# log.net
KiCad netlist of a schematic drawn in Altium Designer
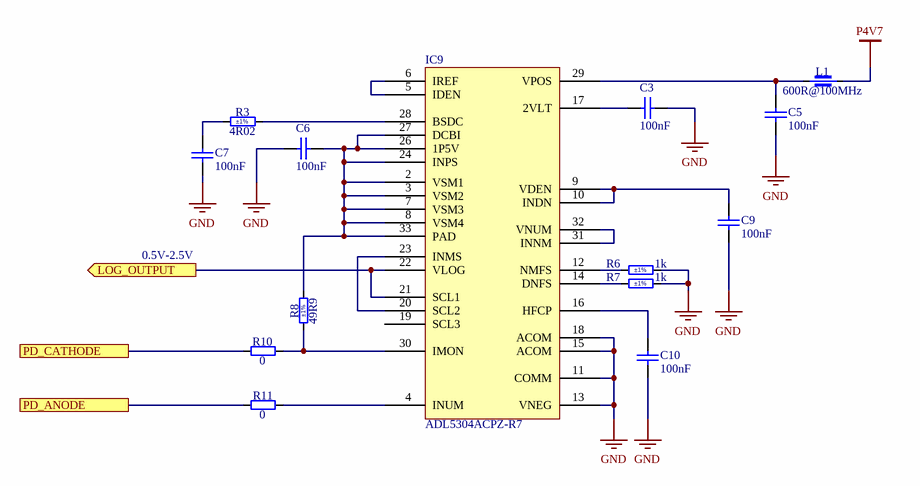
[diagram p0: log.SchDoc]

(export (version "E")
  (design (tool "Eeschema 10.0.6"))
  (components
    (comp (ref "C3")
      (value "100nF")
      (footprint "CAPC1005X55N")
      (description "Non-polarised capacitor")
      (fields
        (field (name "TOLERANCE") "±10%")
        (field (name "VOLTAGE") "16V")
        (field (name "AUTHOR") "CERN DEM JLC")
      )
      (libsource (lib "Capacitors") (part "Capacitor - non polarized"))
    )
    (comp (ref "C5")
      (value "100nF")
      (footprint "CAPC1005X55N")
      (description "Non-polarised capacitor")
      (fields
        (field (name "TOLERANCE") "±10%")
        (field (name "VOLTAGE") "16V")
        (field (name "AUTHOR") "CERN DEM JLC")
      )
      (libsource (lib "Capacitors") (part "Capacitor - non polarized"))
    )
    (comp (ref "C6")
      (value "100nF")
      (footprint "CAPC1005X55N")
      (description "Non-polarised capacitor")
      (fields
        (field (name "TOLERANCE") "±10%")
        (field (name "VOLTAGE") "16V")
        (field (name "AUTHOR") "CERN DEM JLC")
      )
      (libsource (lib "Capacitors") (part "Capacitor - non polarized"))
    )
    (comp (ref "C7")
      (value "100nF")
      (footprint "CAPC1005X55N")
      (description "Non-polarised capacitor")
      (fields
        (field (name "TOLERANCE") "±10%")
        (field (name "VOLTAGE") "16V")
        (field (name "AUTHOR") "CERN DEM JLC")
      )
      (libsource (lib "Capacitors") (part "Capacitor - non polarized"))
    )
    (comp (ref "C9")
      (value "100nF")
      (footprint "CAPC1005X55N")
      (description "Non-polarised capacitor")
      (fields
        (field (name "TOLERANCE") "±10%")
        (field (name "VOLTAGE") "16V")
        (field (name "AUTHOR") "CERN DEM JLC")
      )
      (libsource (lib "Capacitors") (part "Capacitor - non polarized"))
    )
    (comp (ref "C10")
      (value "100nF")
      (footprint "CAPC1005X55N")
      (description "Non-polarised capacitor")
      (fields
        (field (name "TOLERANCE") "±10%")
        (field (name "VOLTAGE") "16V")
        (field (name "AUTHOR") "CERN DEM JLC")
      )
      (libsource (lib "Capacitors") (part "Capacitor - non polarized"))
    )
    (comp (ref "IC9")
      (value "ADL5304ACPZ-R7")
      (footprint "LFCSP32")
      (description "SP Amp LOG Amp Single 5.5V 32-Pin LFCSP EP T/R")
      (fields (field (name "MANUFACTURER") "Analog Devices"))
      (libsource (lib "DiPho") (part "ADL5304ACPZ-R7"))
    )
    (comp (ref "L1")
      (value "600R@100MHz")
      (footprint "INDC1005X55N")
      (fields
        (field (name "PART NUMBER") "IND0402_MURATA_BLM15HD601SN1")
        (field (name "POWER") "300mA")
        (field (name "TOLERANCE") "±25%")
        (field (name "AUTHOR") "CERN DEM JLC")
      )
      (libsource (lib "Inductors & Transformers") (part "Ferrite Bead"))
    )
    (comp (ref "R3")
      (value "4R02")
      (footprint "RESC1005X40N")
      (description "Resistor - 1%")
      (fields
        (field (name "TOLERANCE") "±1%")
        (field (name "PART NUMBER") "R0402_4R02_1%_0.063W_100PPM")
        (field (name "POWER") "0.063W")
        (field (name "AUTHOR") "CERN DEM BC")
      )
      (libsource (lib "Resistors") (part "Resistor - 1%"))
    )
    (comp (ref "R6")
      (value "1k")
      (footprint "RESC1005X40N")
      (description "Resistor - 1%")
      (fields
        (field (name "TOLERANCE") "±1%")
        (field (name "PART NUMBER") "R0402_1K_1%_0.0625W_100PPM")
        (field (name "POWER") "0.0625W")
        (field (name "AUTHOR") "CERN DEM JLC")
      )
      (libsource (lib "Resistors") (part "Resistor - 1%"))
    )
    (comp (ref "R7")
      (value "1k")
      (footprint "RESC1005X40N")
      (description "Resistor - 1%")
      (fields
        (field (name "TOLERANCE") "±1%")
        (field (name "PART NUMBER") "R0402_1K_1%_0.0625W_100PPM")
        (field (name "POWER") "0.0625W")
        (field (name "AUTHOR") "CERN DEM JLC")
      )
      (libsource (lib "Resistors") (part "Resistor - 1%"))
    )
    (comp (ref "R8")
      (value "49R9")
      (footprint "RESC1005X40N")
      (description "Resistor - 1%")
      (fields
        (field (name "TOLERANCE") "±1%")
        (field (name "PART NUMBER") "R0402_49R9_1%_0.0625W_100PPM")
        (field (name "POWER") "0.0625W")
        (field (name "AUTHOR") "CERN DEM JLC")
      )
      (libsource (lib "Resistors") (part "Resistor - 1%"))
    )
    (comp (ref "R10")
      (value "0")
      (footprint "RESC1005X40N")
      (description "Resistor")
      (fields
        (field (name "PART NUMBER") "R0402_0R_JUMPER")
        (field (name "MANUFACTURER") "GENERIC")
        (field (name "AUTHOR") "CERN DEM JLC")
      )
      (libsource (lib "Resistors") (part "Resistor"))
    )
    (comp (ref "R11")
      (value "0")
      (footprint "RESC1005X40N")
      (description "Resistor")
      (fields
        (field (name "PART NUMBER") "R0402_0R_JUMPER")
        (field (name "MANUFACTURER") "GENERIC")
        (field (name "AUTHOR") "CERN DEM JLC")
      )
      (libsource (lib "Resistors") (part "Resistor"))
    )
  )
  (nets
    (net (code "1") (name "/LOG_OUTPUT") (class "Default")
      (node (ref "IC9") (pin "21") (pinfunction "SCL1_21") (pintype "passive"))
      (node (ref "IC9") (pin "22") (pinfunction "VLOG_22") (pintype "passive"))
    )
    (net (code "2") (name "/PD_ANODE") (class "Default")
      (node (ref "R11") (pin "1") (pinfunction "1_1") (pintype "passive"))
    )
    (net (code "3") (name "/PD_CATHODE") (class "Default")
      (node (ref "R10") (pin "1") (pinfunction "1_1") (pintype "passive"))
    )
    (net (code "4") (name "GND") (class "Default")
      (node (ref "C10") (pin "1") (pinfunction "1_1") (pintype "passive"))
      (node (ref "C3") (pin "1") (pinfunction "1_1") (pintype "passive"))
      (node (ref "C5") (pin "1") (pinfunction "1_1") (pintype "passive"))
      (node (ref "C6") (pin "2") (pinfunction "2_2") (pintype "passive"))
      (node (ref "C7") (pin "2") (pinfunction "2_2") (pintype "passive"))
      (node (ref "C9") (pin "1") (pinfunction "1_1") (pintype "passive"))
      (node (ref "IC9") (pin "11") (pinfunction "COMM_11") (pintype "passive"))
      (node (ref "IC9") (pin "13") (pinfunction "VNEG_13") (pintype "passive"))
      (node (ref "IC9") (pin "15") (pinfunction "ACOM_15") (pintype "passive"))
      (node (ref "IC9") (pin "18") (pinfunction "ACOM_18") (pintype "passive"))
      (node (ref "R6") (pin "2") (pinfunction "2_2") (pintype "passive"))
      (node (ref "R7") (pin "2") (pinfunction "2_2") (pintype "passive"))
    )
    (net (code "5") (name "Net-(C7-Pad1)") (class "Default")
      (node (ref "C7") (pin "1") (pinfunction "1_1") (pintype "passive"))
      (node (ref "R3") (pin "1") (pinfunction "1_1") (pintype "passive"))
    )
    (net (code "6") (name "Net-(IC9-1P5V)") (class "Default")
      (node (ref "C6") (pin "1") (pinfunction "1_1") (pintype "passive"))
      (node (ref "IC9") (pin "2") (pinfunction "VSM1_2") (pintype "passive"))
      (node (ref "IC9") (pin "24") (pinfunction "INPS_24") (pintype "passive"))
      (node (ref "IC9") (pin "26") (pinfunction "1P5V_26") (pintype "passive"))
      (node (ref "IC9") (pin "27") (pinfunction "DCBI_27") (pintype "passive"))
      (node (ref "IC9") (pin "3") (pinfunction "VSM2_3") (pintype "passive"))
      (node (ref "IC9") (pin "33") (pinfunction "PAD_33") (pintype "passive"))
      (node (ref "IC9") (pin "7") (pinfunction "VSM3_7") (pintype "passive"))
      (node (ref "IC9") (pin "8") (pinfunction "VSM4_8") (pintype "passive"))
      (node (ref "R8") (pin "2") (pinfunction "2_2") (pintype "passive"))
    )
    (net (code "7") (name "Net-(IC9-2VLT)") (class "Default")
      (node (ref "C3") (pin "2") (pinfunction "2_2") (pintype "passive"))
      (node (ref "IC9") (pin "17") (pinfunction "2VLT_17") (pintype "passive"))
    )
    (net (code "8") (name "Net-(IC9-BSDC)") (class "Default")
      (node (ref "IC9") (pin "28") (pinfunction "BSDC_28") (pintype "passive"))
      (node (ref "R3") (pin "2") (pinfunction "2_2") (pintype "passive"))
    )
    (net (code "9") (name "Net-(IC9-DNFS)") (class "Default")
      (node (ref "IC9") (pin "14") (pinfunction "DNFS_14") (pintype "passive"))
      (node (ref "R7") (pin "1") (pinfunction "1_1") (pintype "passive"))
    )
    (net (code "10") (name "Net-(IC9-HFCP)") (class "Default")
      (node (ref "C10") (pin "2") (pinfunction "2_2") (pintype "passive"))
      (node (ref "IC9") (pin "16") (pinfunction "HFCP_16") (pintype "passive"))
    )
    (net (code "11") (name "Net-(IC9-IDEN)") (class "Default")
      (node (ref "IC9") (pin "5") (pinfunction "IDEN_5") (pintype "passive"))
      (node (ref "IC9") (pin "6") (pinfunction "IREF_6") (pintype "passive"))
    )
    (net (code "12") (name "Net-(IC9-IMON)") (class "Default")
      (node (ref "IC9") (pin "30") (pinfunction "IMON_30") (pintype "passive"))
      (node (ref "R10") (pin "2") (pinfunction "2_2") (pintype "passive"))
      (node (ref "R8") (pin "1") (pinfunction "1_1") (pintype "passive"))
    )
    (net (code "13") (name "Net-(IC9-INDN)") (class "Default")
      (node (ref "C9") (pin "2") (pinfunction "2_2") (pintype "passive"))
      (node (ref "IC9") (pin "10") (pinfunction "INDN_10") (pintype "passive"))
      (node (ref "IC9") (pin "9") (pinfunction "VDEN_9") (pintype "passive"))
    )
    (net (code "14") (name "Net-(IC9-INMS)") (class "Default")
      (node (ref "IC9") (pin "20") (pinfunction "SCL2_20") (pintype "passive"))
      (node (ref "IC9") (pin "23") (pinfunction "INMS_23") (pintype "passive"))
    )
    (net (code "15") (name "Net-(IC9-INNM)") (class "Default")
      (node (ref "IC9") (pin "31") (pinfunction "INNM_31") (pintype "passive"))
      (node (ref "IC9") (pin "32") (pinfunction "VNUM_32") (pintype "passive"))
    )
    (net (code "16") (name "Net-(IC9-INUM)") (class "Default")
      (node (ref "IC9") (pin "4") (pinfunction "INUM_4") (pintype "passive"))
      (node (ref "R11") (pin "2") (pinfunction "2_2") (pintype "passive"))
    )
    (net (code "17") (name "Net-(IC9-NMFS)") (class "Default")
      (node (ref "IC9") (pin "12") (pinfunction "NMFS_12") (pintype "passive"))
      (node (ref "R6") (pin "1") (pinfunction "1_1") (pintype "passive"))
    )
    (net (code "18") (name "Net-(IC9-VPOS)") (class "Default")
      (node (ref "C5") (pin "2") (pinfunction "2_2") (pintype "passive"))
      (node (ref "IC9") (pin "29") (pinfunction "VPOS_29") (pintype "passive"))
      (node (ref "L1") (pin "1") (pinfunction "1_1") (pintype "passive"))
    )
    (net (code "19") (name "P4V7") (class "Default")
      (node (ref "L1") (pin "2") (pinfunction "2_2") (pintype "passive"))
    )
    (net (code "20") (name "unconnected-(IC9-SCL3-Pad19)") (class "Default")
      (node (ref "IC9") (pin "19") (pinfunction "SCL3_19") (pintype "passive"))
    )
  )
)
